# Mic_Eingangsstufe.net
KiCad netlist of a schematic drawn in Altium Designer
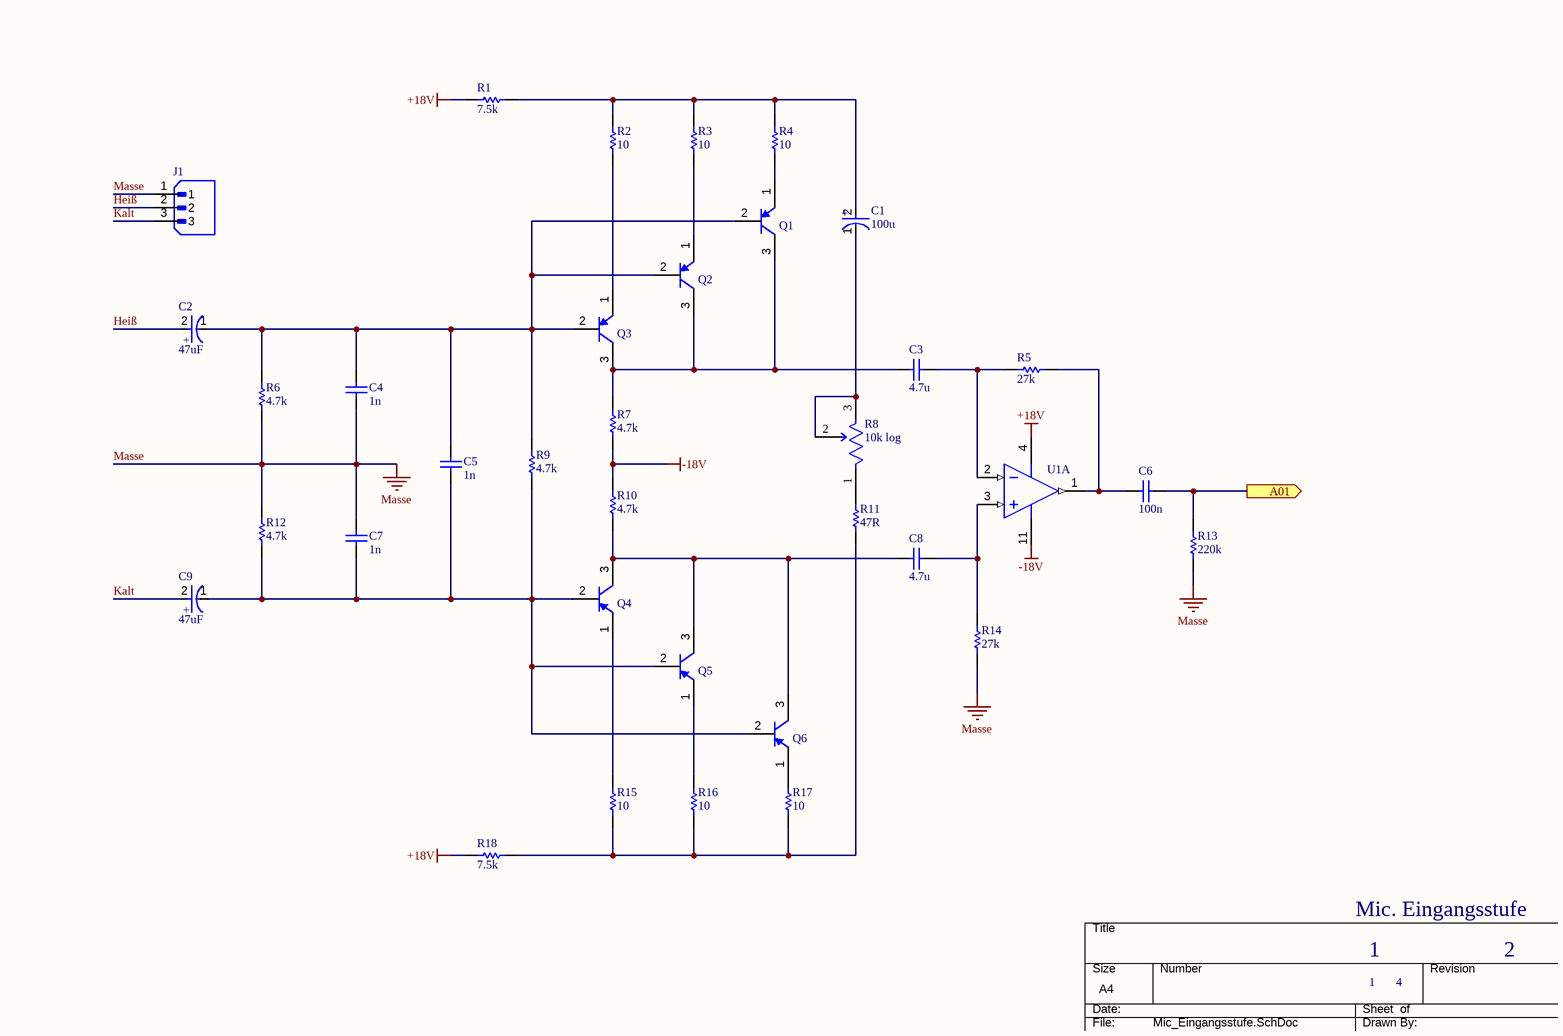
[diagram p0: Mic_Eingangsstufe.SchDoc]

(export (version "E")
  (design (tool "Eeschema 10.0.6"))
  (components
    (comp (ref "C1")
      (value "100u")
      (footprint "4141 Kondensator")
      (description "4141Kondensator")
      (libsource (lib "Bauteile") (part "4141 Kondensator"))
    )
    (comp (ref "C2")
      (value "47uF")
      (footprint "2626 Kondensator")
      (description "2626 Kondensator d=6.6mm")
      (fields (field (name "VOLTAGE") "25V") (field (name "TOLERANCE") "20%"))
      (libsource (lib "Bauteile") (part "2626 Kondensator"))
    )
    (comp (ref "C3")
      (value "4.7u")
      (footprint "0805")
      (description "0805 Kondensator")
      (libsource (lib "Bauteile") (part "0805 Kondensator"))
    )
    (comp (ref "C4")
      (value "1n")
      (footprint "0805")
      (description "0805 Kondensator")
      (libsource (lib "Bauteile") (part "0805 Kondensator"))
    )
    (comp (ref "C5")
      (value "1n")
      (footprint "0805")
      (description "0805 Kondensator")
      (libsource (lib "Bauteile") (part "0805 Kondensator"))
    )
    (comp (ref "C6")
      (value "100n")
      (footprint "0805")
      (description "0805 Kondensator")
      (libsource (lib "Bauteile") (part "0805 Kondensator"))
    )
    (comp (ref "C7")
      (value "1n")
      (footprint "0805")
      (description "0805 Kondensator")
      (libsource (lib "Bauteile") (part "0805 Kondensator"))
    )
    (comp (ref "C8")
      (value "4.7u")
      (footprint "0805")
      (description "0805 Kondensator")
      (libsource (lib "Bauteile") (part "0805 Kondensator"))
    )
    (comp (ref "C9")
      (value "47uF")
      (footprint "2626 Kondensator")
      (description "2626 Kondensator d=6.6mm")
      (fields (field (name "VOLTAGE") "25V") (field (name "TOLERANCE") "20%"))
      (libsource (lib "Bauteile") (part "2626 Kondensator"))
    )
    (comp (ref "J1")
      (value "Connector x3")
      (footprint "Connector x3")
      (description "Connector Header Through Hole 3 position 0.100 (2.54mm)")
      (fields (field (name "MF") "JST Sales") (field (name "MP") "B3B-XH-A"))
      (libsource (lib "Bauteile") (part "Connector x3"))
    )
    (comp (ref "Q1")
      (value "PNP")
      (footprint "Buchsenleiste 3 Fach PNP TO92")
      (description "TO-92 PNP Bipolar Transistor")
      (libsource (lib "Bauteile") (part "TO-92 PNP BUchsenleiste"))
    )
    (comp (ref "Q2")
      (value "PNP")
      (footprint "Buchsenleiste 3 Fach PNP TO92")
      (description "TO-92 PNP Bipolar Transistor")
      (libsource (lib "Bauteile") (part "TO-92 PNP BUchsenleiste"))
    )
    (comp (ref "Q3")
      (value "PNP")
      (footprint "Buchsenleiste 3 Fach PNP TO92")
      (description "TO-92 PNP Bipolar Transistor")
      (libsource (lib "Bauteile") (part "TO-92 PNP BUchsenleiste"))
    )
    (comp (ref "Q4")
      (value "PNP")
      (footprint "Buchsenleiste 3 Fach PNP TO92")
      (description "TO-92 PNP Bipolar Transistor")
      (libsource (lib "Bauteile") (part "TO-92 PNP BUchsenleiste"))
    )
    (comp (ref "Q5")
      (value "PNP")
      (footprint "Buchsenleiste 3 Fach PNP TO92")
      (description "TO-92 PNP Bipolar Transistor")
      (libsource (lib "Bauteile") (part "TO-92 PNP BUchsenleiste"))
    )
    (comp (ref "Q6")
      (value "PNP")
      (footprint "Buchsenleiste 3 Fach PNP TO92")
      (description "TO-92 PNP Bipolar Transistor")
      (libsource (lib "Bauteile") (part "TO-92 PNP BUchsenleiste"))
    )
    (comp (ref "R1")
      (value "7.5k")
      (footprint "0805")
      (description "0805 Widerstand")
      (libsource (lib "Bauteile") (part "0805 Widerstand"))
    )
    (comp (ref "R2")
      (value "10")
      (footprint "0805")
      (description "0805 Widerstand")
      (libsource (lib "Bauteile") (part "0805 Widerstand"))
    )
    (comp (ref "R3")
      (value "10")
      (footprint "0805")
      (description "0805 Widerstand")
      (libsource (lib "Bauteile") (part "0805 Widerstand"))
    )
    (comp (ref "R4")
      (value "10")
      (footprint "0805")
      (description "0805 Widerstand")
      (libsource (lib "Bauteile") (part "0805 Widerstand"))
    )
    (comp (ref "R5")
      (value "27k")
      (footprint "0805")
      (description "0805 Widerstand")
      (libsource (lib "Bauteile") (part "0805 Widerstand"))
    )
    (comp (ref "R6")
      (value "4.7k")
      (footprint "0805")
      (description "0805 Widerstand")
      (libsource (lib "Bauteile") (part "0805 Widerstand"))
    )
    (comp (ref "R7")
      (value "4.7k")
      (footprint "0805")
      (description "0805 Widerstand")
      (libsource (lib "Bauteile") (part "0805 Widerstand"))
    )
    (comp (ref "R8")
      (value "10k log")
      (footprint "Connector x3")
      (description "Potentiometer")
      (libsource (lib "Bauteile") (part "Potentiometer Buchsenleiste"))
    )
    (comp (ref "R9")
      (value "4.7k")
      (footprint "0805")
      (description "0805 Widerstand")
      (libsource (lib "Bauteile") (part "0805 Widerstand"))
    )
    (comp (ref "R10")
      (value "4.7k")
      (footprint "0805")
      (description "0805 Widerstand")
      (libsource (lib "Bauteile") (part "0805 Widerstand"))
    )
    (comp (ref "R11")
      (value "47R")
      (footprint "0805")
      (description "0805 Widerstand")
      (libsource (lib "Bauteile") (part "0805 Widerstand"))
    )
    (comp (ref "R12")
      (value "4.7k")
      (footprint "0805")
      (description "0805 Widerstand")
      (libsource (lib "Bauteile") (part "0805 Widerstand"))
    )
    (comp (ref "R13")
      (value "220k")
      (footprint "0805")
      (description "0805 Widerstand")
      (libsource (lib "Bauteile") (part "0805 Widerstand"))
    )
    (comp (ref "R14")
      (value "27k")
      (footprint "0805")
      (description "0805 Widerstand")
      (libsource (lib "Bauteile") (part "0805 Widerstand"))
    )
    (comp (ref "R15")
      (value "10")
      (footprint "0805")
      (description "0805 Widerstand")
      (libsource (lib "Bauteile") (part "0805 Widerstand"))
    )
    (comp (ref "R16")
      (value "10")
      (footprint "0805")
      (description "0805 Widerstand")
      (libsource (lib "Bauteile") (part "0805 Widerstand"))
    )
    (comp (ref "R17")
      (value "10")
      (footprint "0805")
      (description "0805 Widerstand")
      (libsource (lib "Bauteile") (part "0805 Widerstand"))
    )
    (comp (ref "R18")
      (value "7.5k")
      (footprint "0805")
      (description "0805 Widerstand")
      (libsource (lib "Bauteile") (part "0805 Widerstand"))
    )
    (comp (ref "U1")
      (value "OPA4134UA")
      (footprint "DIP14 IC Socket")
      (fields (field (name "MANUFACTURER") "Texas Instruments"))
      (libsource (lib "Bauteile") (part "SOIC OPA4134UA"))
    )
  )
  (nets
    (net (code "1") (name "+18V") (class "Default")
      (node (ref "R1") (pin "1") (pinfunction "1_1") (pintype "passive"))
      (node (ref "R18") (pin "1") (pinfunction "1_1") (pintype "passive"))
      (node (ref "U1") (pin "4") (pinfunction "V+_4") (pintype "power_in"))
    )
    (net (code "2") (name "-18V") (class "Default")
      (node (ref "R10") (pin "2") (pinfunction "2_2") (pintype "passive"))
      (node (ref "R7") (pin "1") (pinfunction "1_1") (pintype "passive"))
      (node (ref "U1") (pin "11") (pinfunction "V-_11") (pintype "power_in"))
    )
    (net (code "3") (name "/A01") (class "Default")
      (node (ref "C6") (pin "2") (pinfunction "2_2") (pintype "passive"))
      (node (ref "R13") (pin "2") (pinfunction "2_2") (pintype "passive"))
    )
    (net (code "4") (name "/Heiß") (class "Default")
      (node (ref "C2") (pin "2") (pinfunction "A_2") (pintype "passive"))
      (node (ref "J1") (pin "2") (pinfunction "2_2") (pintype "passive"))
    )
    (net (code "5") (name "/Kalt") (class "Default")
      (node (ref "C9") (pin "2") (pinfunction "A_2") (pintype "passive"))
      (node (ref "J1") (pin "3") (pinfunction "3_3") (pintype "passive"))
    )
    (net (code "6") (name "Masse") (class "Default")
      (node (ref "C4") (pin "1") (pinfunction "1_1") (pintype "passive"))
      (node (ref "C7") (pin "2") (pinfunction "2_2") (pintype "passive"))
      (node (ref "J1") (pin "1") (pinfunction "1_1") (pintype "passive"))
      (node (ref "R12") (pin "2") (pinfunction "2_2") (pintype "passive"))
      (node (ref "R13") (pin "1") (pinfunction "1_1") (pintype "passive"))
      (node (ref "R14") (pin "1") (pinfunction "1_1") (pintype "passive"))
      (node (ref "R6") (pin "1") (pinfunction "1_1") (pintype "passive"))
    )
    (net (code "7") (name "Net-(C1-A)") (class "Default")
      (node (ref "C1") (pin "2") (pinfunction "A_2") (pintype "passive"))
      (node (ref "R1") (pin "2") (pinfunction "2_2") (pintype "passive"))
      (node (ref "R2") (pin "1") (pinfunction "1_1") (pintype "passive"))
      (node (ref "R3") (pin "1") (pinfunction "1_1") (pintype "passive"))
      (node (ref "R4") (pin "1") (pinfunction "1_1") (pintype "passive"))
    )
    (net (code "8") (name "Net-(C1-C)") (class "Default")
      (node (ref "C1") (pin "1") (pinfunction "C_1") (pintype "passive"))
      (node (ref "R8") (pin "2") (pinfunction "b_2") (pintype "passive"))
      (node (ref "R8") (pin "3") (pinfunction "c_3") (pintype "passive"))
    )
    (net (code "9") (name "Net-(C2-C)") (class "Default")
      (node (ref "C2") (pin "1") (pinfunction "C_1") (pintype "passive"))
      (node (ref "C4") (pin "2") (pinfunction "2_2") (pintype "passive"))
      (node (ref "C5") (pin "2") (pinfunction "2_2") (pintype "passive"))
      (node (ref "Q1") (pin "2") (pinfunction "B_2") (pintype "passive"))
      (node (ref "Q2") (pin "2") (pinfunction "B_2") (pintype "passive"))
      (node (ref "Q3") (pin "2") (pinfunction "B_2") (pintype "passive"))
      (node (ref "R6") (pin "2") (pinfunction "2_2") (pintype "passive"))
      (node (ref "R9") (pin "2") (pinfunction "2_2") (pintype "passive"))
    )
    (net (code "10") (name "Net-(C9-C)") (class "Default")
      (node (ref "C5") (pin "1") (pinfunction "1_1") (pintype "passive"))
      (node (ref "C7") (pin "1") (pinfunction "1_1") (pintype "passive"))
      (node (ref "C9") (pin "1") (pinfunction "C_1") (pintype "passive"))
      (node (ref "Q4") (pin "2") (pinfunction "B_2") (pintype "passive"))
      (node (ref "Q5") (pin "2") (pinfunction "B_2") (pintype "passive"))
      (node (ref "Q6") (pin "2") (pinfunction "B_2") (pintype "passive"))
      (node (ref "R12") (pin "1") (pinfunction "1_1") (pintype "passive"))
      (node (ref "R9") (pin "1") (pinfunction "1_1") (pintype "passive"))
    )
    (net (code "11") (name "Net-(Q1-C)") (class "Default")
      (node (ref "C3") (pin "2") (pinfunction "2_2") (pintype "passive"))
      (node (ref "Q1") (pin "3") (pinfunction "C_3") (pintype "passive"))
      (node (ref "Q2") (pin "3") (pinfunction "C_3") (pintype "passive"))
      (node (ref "Q3") (pin "3") (pinfunction "C_3") (pintype "passive"))
      (node (ref "R7") (pin "2") (pinfunction "2_2") (pintype "passive"))
    )
    (net (code "12") (name "Net-(Q1-E)") (class "Default")
      (node (ref "Q1") (pin "1") (pinfunction "E_1") (pintype "passive"))
      (node (ref "R4") (pin "2") (pinfunction "2_2") (pintype "passive"))
    )
    (net (code "13") (name "Net-(Q2-E)") (class "Default")
      (node (ref "Q2") (pin "1") (pinfunction "E_1") (pintype "passive"))
      (node (ref "R3") (pin "2") (pinfunction "2_2") (pintype "passive"))
    )
    (net (code "14") (name "Net-(Q3-E)") (class "Default")
      (node (ref "Q3") (pin "1") (pinfunction "E_1") (pintype "passive"))
      (node (ref "R2") (pin "2") (pinfunction "2_2") (pintype "passive"))
    )
    (net (code "15") (name "Net-(Q4-C)") (class "Default")
      (node (ref "C8") (pin "2") (pinfunction "2_2") (pintype "passive"))
      (node (ref "Q4") (pin "3") (pinfunction "C_3") (pintype "passive"))
      (node (ref "Q5") (pin "3") (pinfunction "C_3") (pintype "passive"))
      (node (ref "Q6") (pin "3") (pinfunction "C_3") (pintype "passive"))
      (node (ref "R10") (pin "1") (pinfunction "1_1") (pintype "passive"))
    )
    (net (code "16") (name "Net-(Q4-E)") (class "Default")
      (node (ref "Q4") (pin "1") (pinfunction "E_1") (pintype "passive"))
      (node (ref "R15") (pin "2") (pinfunction "2_2") (pintype "passive"))
    )
    (net (code "17") (name "Net-(Q5-E)") (class "Default")
      (node (ref "Q5") (pin "1") (pinfunction "E_1") (pintype "passive"))
      (node (ref "R16") (pin "2") (pinfunction "2_2") (pintype "passive"))
    )
    (net (code "18") (name "Net-(Q6-E)") (class "Default")
      (node (ref "Q6") (pin "1") (pinfunction "E_1") (pintype "passive"))
      (node (ref "R17") (pin "2") (pinfunction "2_2") (pintype "passive"))
    )
    (net (code "19") (name "Net-(R8-a)") (class "Default")
      (node (ref "R11") (pin "2") (pinfunction "2_2") (pintype "passive"))
      (node (ref "R8") (pin "1") (pinfunction "a_1") (pintype "passive"))
    )
    (net (code "20") (name "Net-(R11-Pad1)") (class "Default")
      (node (ref "R11") (pin "1") (pinfunction "1_1") (pintype "passive"))
      (node (ref "R15") (pin "1") (pinfunction "1_1") (pintype "passive"))
      (node (ref "R16") (pin "1") (pinfunction "1_1") (pintype "passive"))
      (node (ref "R17") (pin "1") (pinfunction "1_1") (pintype "passive"))
      (node (ref "R18") (pin "2") (pinfunction "2_2") (pintype "passive"))
    )
    (net (code "21") (name "Net-(U1A-IN_A+)") (class "Default")
      (node (ref "C8") (pin "1") (pinfunction "1_1") (pintype "passive"))
      (node (ref "R14") (pin "2") (pinfunction "2_2") (pintype "passive"))
      (node (ref "U1") (pin "3") (pinfunction "IN_A+_3") (pintype "input"))
    )
    (net (code "22") (name "Net-(U1A-IN_A-)") (class "Default")
      (node (ref "C3") (pin "1") (pinfunction "1_1") (pintype "passive"))
      (node (ref "R5") (pin "2") (pinfunction "2_2") (pintype "passive"))
      (node (ref "U1") (pin "2") (pinfunction "IN_A-_2") (pintype "input"))
    )
    (net (code "23") (name "Net-(U1A-OUT_A)") (class "Default")
      (node (ref "C6") (pin "1") (pinfunction "1_1") (pintype "passive"))
      (node (ref "R5") (pin "1") (pinfunction "1_1") (pintype "passive"))
      (node (ref "U1") (pin "1") (pinfunction "OUT_A_1") (pintype "output"))
    )
  )
)
